# Antenna_Switch.net
KiCad netlist of a schematic drawn in Altium Designer
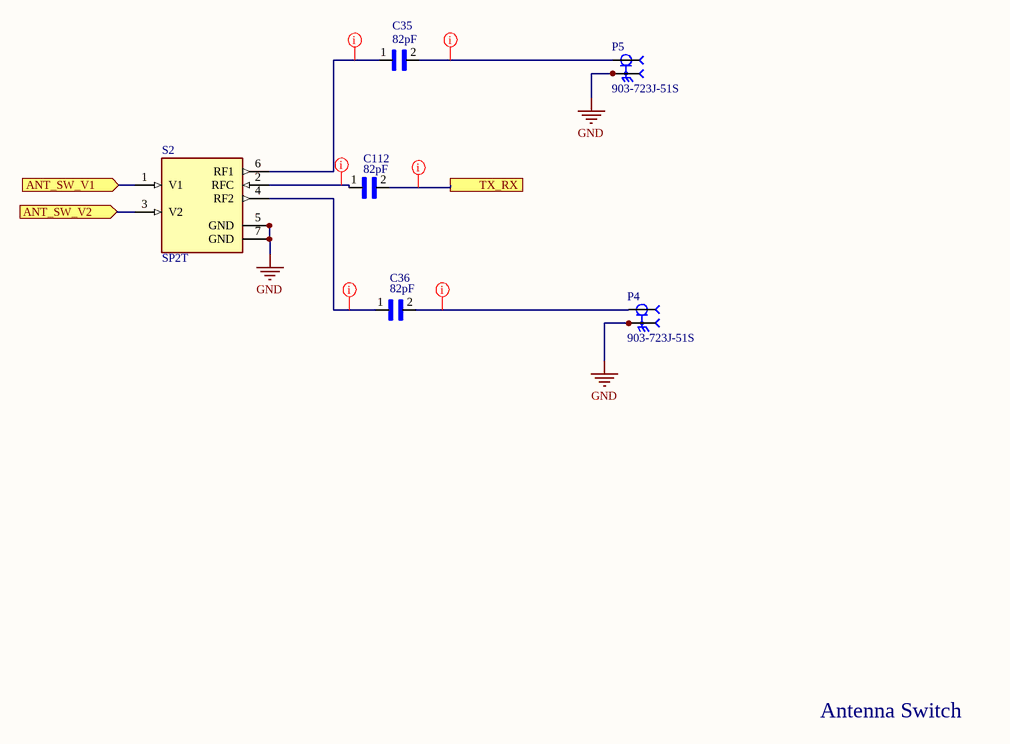
[diagram p0: Antenna Switch.SchDoc]

(export (version "E")
  (design (tool "Eeschema 10.0.6"))
  (components
    (comp (ref "C35")
      (value "82pF")
      (footprint "CAPC1005X55N")
      (description "CAP CER 82PF 50V C0G/NP0 0402")
      (fields (field (name "MP") "GRM1555C1H820GA01J"))
      (libsource (lib "GRM1555C1H820GA01J") (part "GRM1555C1H820GA01J"))
    )
    (comp (ref "C36")
      (value "82pF")
      (footprint "CAPC1005X55N")
      (description "CAP CER 82PF 50V C0G/NP0 0402")
      (fields (field (name "MP") "GRM1555C1H820GA01J"))
      (libsource (lib "GRM1555C1H820GA01J") (part "GRM1555C1H820GA01J"))
    )
    (comp (ref "C112")
      (value "82pF")
      (footprint "CAPC1005X55N")
      (description "CAP CER 82PF 50V C0G/NP0 0402")
      (fields (field (name "MP") "GRM1555C1H820GA01J"))
      (libsource (lib "GRM1555C1H820GA01J") (part "GRM1555C1H820GA01J"))
    )
    (comp (ref "P4")
      (value "903-723J-51S")
      (footprint "AMPHENOL_903-723J-51S")
      (description "SMB Connector Jack, Male Pin 50Ohm Board Edge, End Launch Solder")
      (libsource (lib "903-723J-51S") (part "903-723J-51S"))
    )
    (comp (ref "P5")
      (value "903-723J-51S")
      (footprint "AMPHENOL_903-723J-51S")
      (description "SMB Connector Jack, Male Pin 50Ohm Board Edge, End Launch Solder")
      (libsource (lib "903-723J-51S") (part "903-723J-51S"))
    )
    (comp (ref "S2")
      (value "SP2T")
      (footprint "SW_SKY13431-374LF")
      (description "RF Switch IC WiMax, WLAN SPDT 6GHz 50Ohm 6-DFN (1.5x1.5)")
      (fields (field (name "MP") "SKY13431-374LF") (field (name "MF") "Skyworks Solutions"))
      (libsource (lib "SKY13431-374LF") (part "SKY13431-374LF"))
    )
  )
  (nets
    (net (code "1") (name "/ANT_SW_V1") (class "Default")
      (node (ref "S2") (pin "1") (pinfunction "V1_1") (pintype "input"))
    )
    (net (code "2") (name "/ANT_SW_V2") (class "Default")
      (node (ref "S2") (pin "3") (pinfunction "V2_3") (pintype "input"))
    )
    (net (code "3") (name "/TX_RX") (class "Default")
      (node (ref "C112") (pin "2") (pinfunction "2_2") (pintype "passive"))
    )
    (net (code "4") (name "GND") (class "Default")
      (node (ref "P4") (pin "S1") (pinfunction "SHIELD_S1") (pintype "passive"))
      (node (ref "P4") (pin "S2") (pinfunction "SHIELD_S2") (pintype "passive"))
      (node (ref "P4") (pin "S3") (pinfunction "SHIELD_S3") (pintype "passive"))
      (node (ref "P4") (pin "S4") (pinfunction "SHIELD_S4") (pintype "passive"))
      (node (ref "P4") (pin "S5") (pinfunction "SHIELD_S5") (pintype "passive"))
      (node (ref "P4") (pin "S6") (pinfunction "SHIELD_S6") (pintype "passive"))
      (node (ref "P4") (pin "S7") (pinfunction "SHIELD_S7") (pintype "passive"))
      (node (ref "P4") (pin "S8") (pinfunction "SHIELD_S8") (pintype "passive"))
      (node (ref "P5") (pin "S1") (pinfunction "SHIELD_S1") (pintype "passive"))
      (node (ref "P5") (pin "S2") (pinfunction "SHIELD_S2") (pintype "passive"))
      (node (ref "P5") (pin "S3") (pinfunction "SHIELD_S3") (pintype "passive"))
      (node (ref "P5") (pin "S4") (pinfunction "SHIELD_S4") (pintype "passive"))
      (node (ref "P5") (pin "S5") (pinfunction "SHIELD_S5") (pintype "passive"))
      (node (ref "P5") (pin "S6") (pinfunction "SHIELD_S6") (pintype "passive"))
      (node (ref "P5") (pin "S7") (pinfunction "SHIELD_S7") (pintype "passive"))
      (node (ref "P5") (pin "S8") (pinfunction "SHIELD_S8") (pintype "passive"))
      (node (ref "S2") (pin "5") (pinfunction "GND_5") (pintype "power_in"))
      (node (ref "S2") (pin "7") (pinfunction "GND_7") (pintype "power_in"))
    )
    (net (code "5") (name "Net-(P4-SIG)") (class "Default")
      (node (ref "C36") (pin "2") (pinfunction "2_2") (pintype "passive"))
      (node (ref "P4") (pin "1") (pinfunction "SIG_1") (pintype "passive"))
    )
    (net (code "6") (name "Net-(P5-SIG)") (class "Default")
      (node (ref "C35") (pin "2") (pinfunction "2_2") (pintype "passive"))
      (node (ref "P5") (pin "1") (pinfunction "SIG_1") (pintype "passive"))
    )
    (net (code "7") (name "Net-(S2-RF1)") (class "Default")
      (node (ref "C35") (pin "1") (pinfunction "1_1") (pintype "passive"))
      (node (ref "S2") (pin "6") (pinfunction "RF1_6") (pintype "output"))
    )
    (net (code "8") (name "Net-(S2-RF2)") (class "Default")
      (node (ref "C36") (pin "1") (pinfunction "1_1") (pintype "passive"))
      (node (ref "S2") (pin "4") (pinfunction "RF2_4") (pintype "output"))
    )
    (net (code "9") (name "Net-(S2-RFC)") (class "Default")
      (node (ref "C112") (pin "1") (pinfunction "1_1") (pintype "passive"))
      (node (ref "S2") (pin "2") (pinfunction "RFC_2") (pintype "input"))
    )
  )
)
